# EEprog.net
KiCad netlist of a schematic drawn in EAGLE
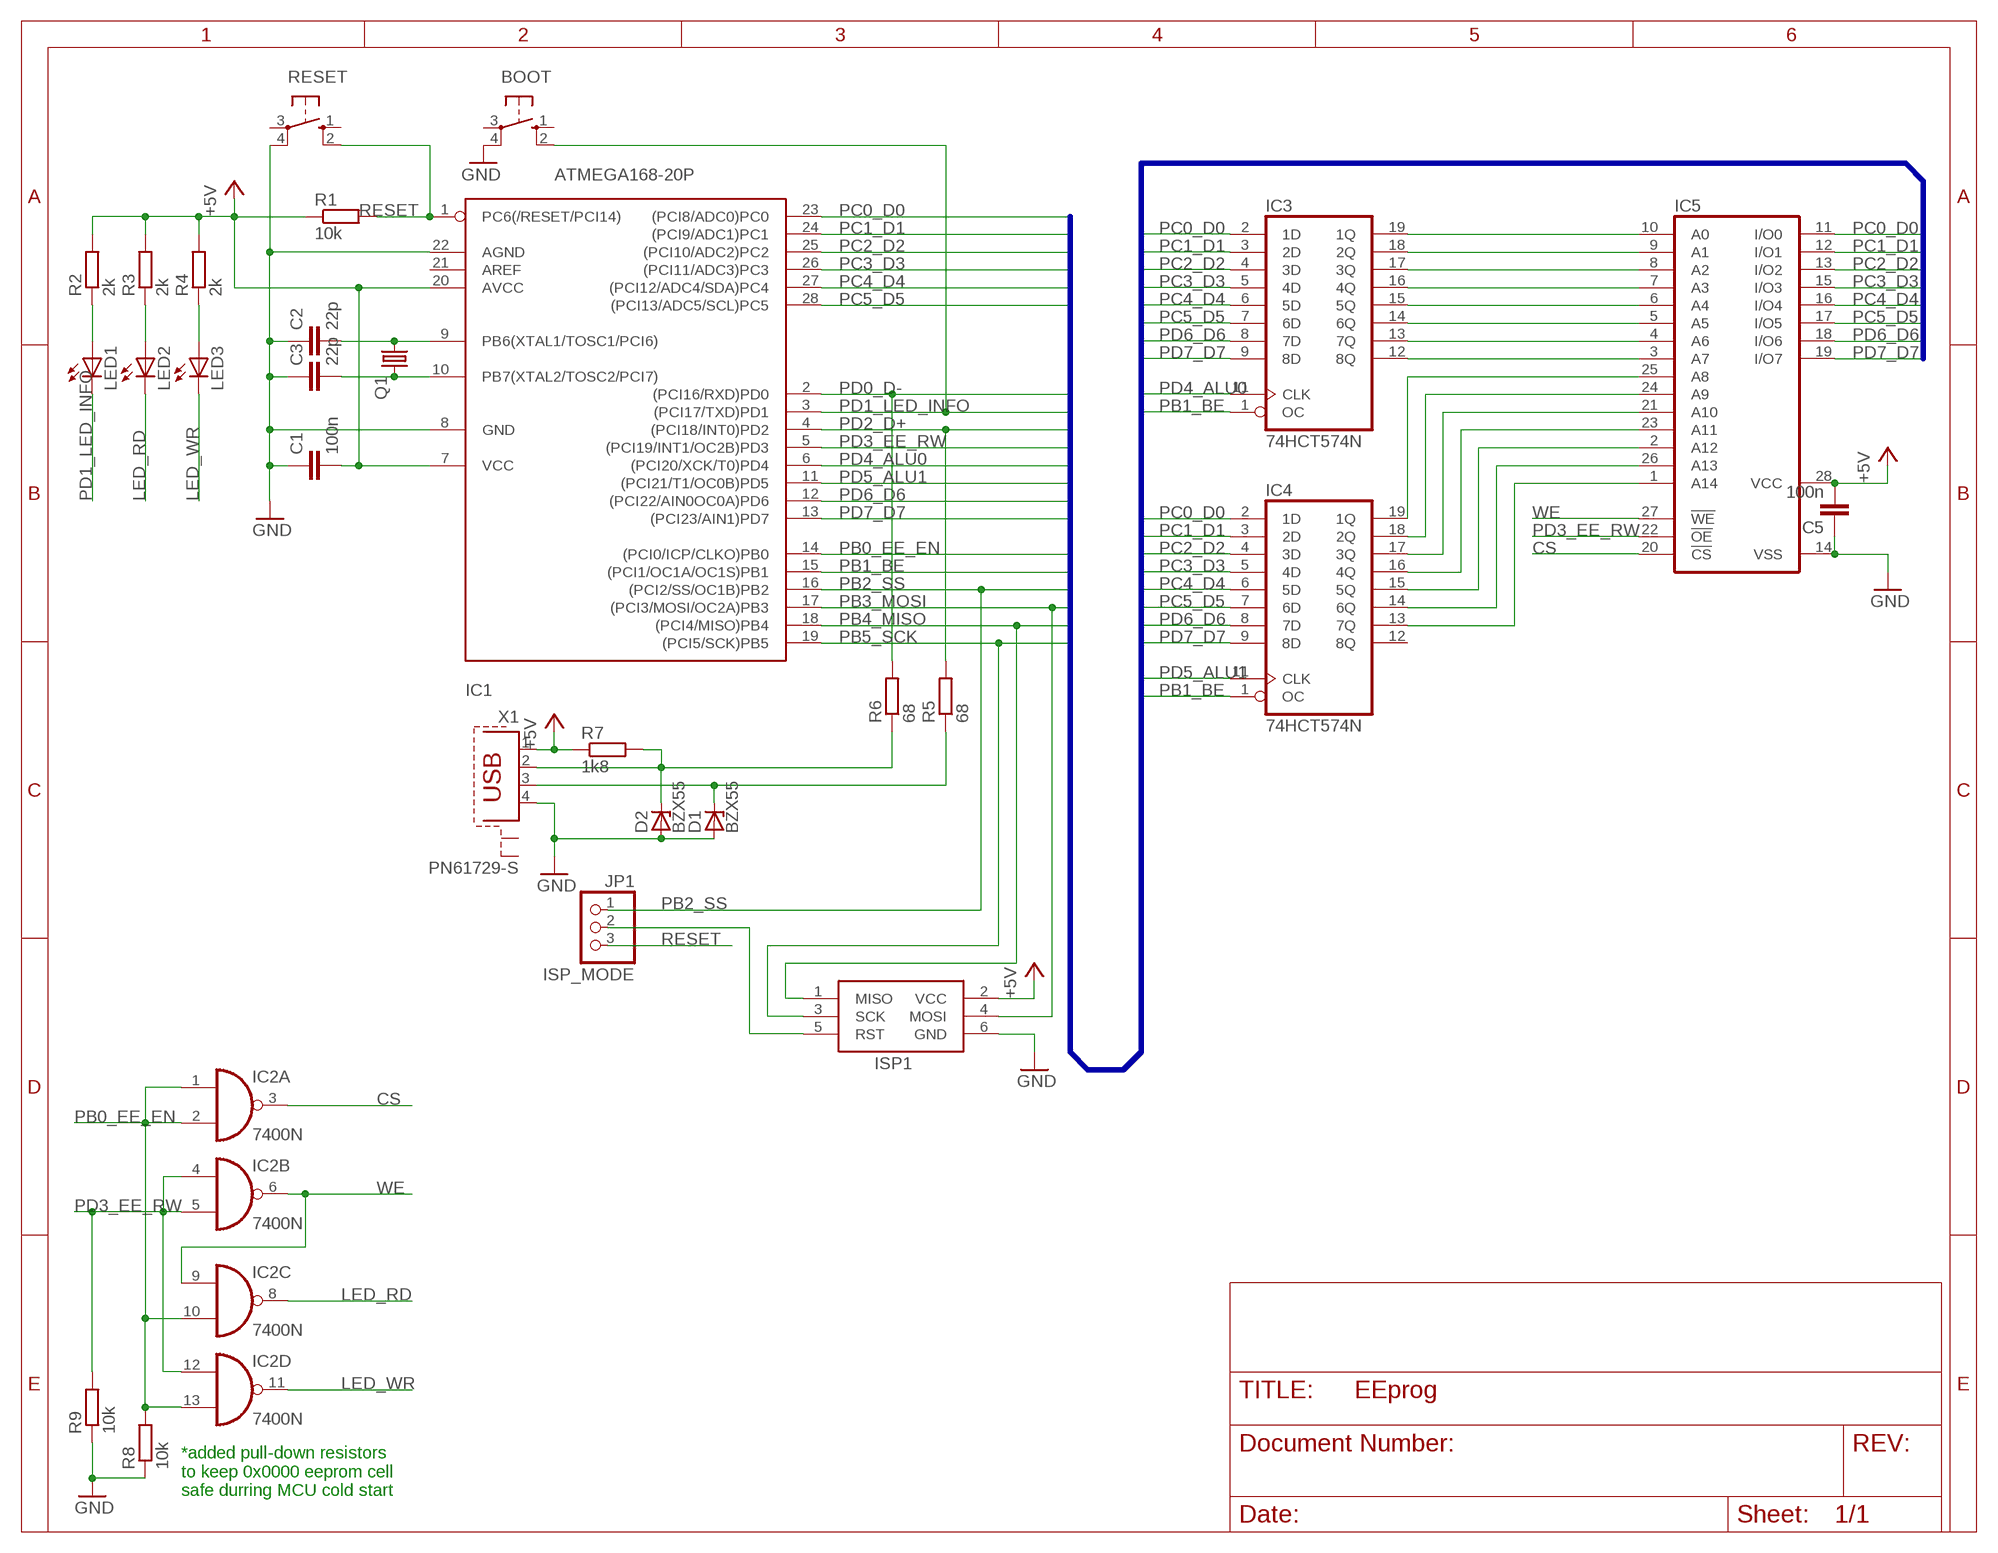
[diagram p0: schematic, sheet 1]

(export (version "E")
  (design (tool "Eeschema 10.0.6"))
  (components
    (comp (ref "BOOT")
      (value "10-XX")
      (footprint "eagle-import:B3F-10XX")
      (fields (field (name "MPN") "B3F-1000"))
      (libsource (lib "eagle-import") (part "10-XX"))
    )
    (comp (ref "C1")
      (value "100n")
      (footprint "eagle-import:C025-025X050")
      (libsource (lib "eagle-import") (part "C-EU025-025X050"))
    )
    (comp (ref "C2")
      (value "22p")
      (footprint "eagle-import:C025-025X050")
      (libsource (lib "eagle-import") (part "C-EU025-025X050"))
    )
    (comp (ref "C3")
      (value "22p")
      (footprint "eagle-import:C025-025X050")
      (libsource (lib "eagle-import") (part "C-EU025-025X050"))
    )
    (comp (ref "C5")
      (value "100n")
      (footprint "eagle-import:C025-025X050")
      (libsource (lib "eagle-import") (part "C-EU025-025X050"))
    )
    (comp (ref "D1")
      (value "BZX55")
      (footprint "eagle-import:DO35Z10")
      (libsource (lib "eagle-import") (part "BZX55"))
    )
    (comp (ref "D2")
      (value "BZX55")
      (footprint "eagle-import:DO35Z10")
      (libsource (lib "eagle-import") (part "BZX55"))
    )
    (comp (ref "IC1")
      (value "ATMEGA168-20P")
      (footprint "eagle-import:DIL28-3")
      (libsource (lib "eagle-import") (part "ATMEGA168P-20"))
    )
    (comp (ref "IC2")
      (value "7400N")
      (footprint "eagle-import:DIL14")
      (libsource (lib "eagle-import") (part "7400N"))
    )
    (comp (ref "IC3")
      (value "74HCT574N")
      (footprint "eagle-import:DIL20")
      (libsource (lib "eagle-import") (part "74574NHCT"))
    )
    (comp (ref "IC4")
      (value "74HCT574N")
      (footprint "eagle-import:DIL20")
      (libsource (lib "eagle-import") (part "74574NHCT"))
    )
    (comp (ref "IC5")
      (value "62256P")
      (footprint "eagle-import:DIL28-6")
      (libsource (lib "eagle-import") (part "62256P"))
    )
    (comp (ref "ISP1")
      (value "AVRISP-BOX")
      (footprint "eagle-import:AVRISP-BOX")
      (libsource (lib "eagle-import") (part "AVRISP-BOX"))
    )
    (comp (ref "JP1")
      (value "ISP_MODE")
      (footprint "eagle-import:1X03")
      (libsource (lib "eagle-import") (part "PINHD-1X3"))
    )
    (comp (ref "LED1")
      (value "LED3MM")
      (footprint "eagle-import:LED3MM")
      (libsource (lib "eagle-import") (part "LED3MM"))
    )
    (comp (ref "LED2")
      (value "LED3MM")
      (footprint "eagle-import:LED3MM")
      (libsource (lib "eagle-import") (part "LED3MM"))
    )
    (comp (ref "LED3")
      (value "LED3MM")
      (footprint "eagle-import:LED3MM")
      (libsource (lib "eagle-import") (part "LED3MM"))
    )
    (comp (ref "Q1")
      (value "CRYSTALHC49S")
      (footprint "eagle-import:HC49_S")
      (libsource (lib "eagle-import") (part "CRYSTALHC49S"))
    )
    (comp (ref "R1")
      (value "10k")
      (footprint "eagle-import:0204_7")
      (libsource (lib "eagle-import") (part "R-EU_0204/7"))
    )
    (comp (ref "R2")
      (value "2k")
      (footprint "eagle-import:0204_7")
      (libsource (lib "eagle-import") (part "R-EU_0204/7"))
    )
    (comp (ref "R3")
      (value "2k")
      (footprint "eagle-import:0204_7")
      (libsource (lib "eagle-import") (part "R-EU_0204/7"))
    )
    (comp (ref "R4")
      (value "2k")
      (footprint "eagle-import:0204_7")
      (libsource (lib "eagle-import") (part "R-EU_0204/7"))
    )
    (comp (ref "R5")
      (value "68")
      (footprint "eagle-import:0204_7")
      (libsource (lib "eagle-import") (part "R-EU_0204/7"))
    )
    (comp (ref "R6")
      (value "68")
      (footprint "eagle-import:0204_7")
      (libsource (lib "eagle-import") (part "R-EU_0204/7"))
    )
    (comp (ref "R7")
      (value "1k8")
      (footprint "eagle-import:0204_7")
      (libsource (lib "eagle-import") (part "R-EU_0204/7"))
    )
    (comp (ref "R8")
      (value "10k")
      (footprint "eagle-import:0204_7")
      (libsource (lib "eagle-import") (part "R-EU_0204/7"))
    )
    (comp (ref "R9")
      (value "10k")
      (footprint "eagle-import:0204_7")
      (libsource (lib "eagle-import") (part "R-EU_0204/7"))
    )
    (comp (ref "RESET")
      (value "10-XX")
      (footprint "eagle-import:B3F-10XX")
      (fields (field (name "MPN") "B3F-1000"))
      (libsource (lib "eagle-import") (part "10-XX"))
    )
    (comp (ref "X1")
      (value "PN61729-S")
      (footprint "eagle-import:PN61729-S")
      (libsource (lib "eagle-import") (part "PN61729-S"))
    )
  )
  (nets
    (net (code "1") (name "+5V") (class "Default")
      (node (ref "C1") (pin "2") (pinfunction "2_2") (pintype "passive"))
      (node (ref "C5") (pin "2") (pinfunction "2_2") (pintype "passive"))
      (node (ref "IC1") (pin "20") (pinfunction "AVCC_20") (pintype "bidirectional"))
      (node (ref "IC1") (pin "7") (pinfunction "VCC_7") (pintype "bidirectional"))
      (node (ref "IC5") (pin "28") (pinfunction "VCC_28") (pintype "power_in"))
      (node (ref "ISP1") (pin "2") (pinfunction "VCC_2") (pintype "power_in"))
      (node (ref "R1") (pin "1") (pinfunction "1_1") (pintype "passive"))
      (node (ref "R2") (pin "2") (pinfunction "2_2") (pintype "passive"))
      (node (ref "R3") (pin "2") (pinfunction "2_2") (pintype "passive"))
      (node (ref "R4") (pin "2") (pinfunction "2_2") (pintype "passive"))
      (node (ref "R7") (pin "1") (pinfunction "1_1") (pintype "passive"))
      (node (ref "X1") (pin "1") (pinfunction "1_1") (pintype "passive"))
    )
    (net (code "2") (name "/CS") (class "Default")
      (node (ref "IC2") (pin "3") (pinfunction "O_3") (pintype "output"))
      (node (ref "IC5") (pin "20") (pinfunction "~{CS}_20") (pintype "input"))
    )
    (net (code "3") (name "/LED_RD") (class "Default")
      (node (ref "IC2") (pin "8") (pinfunction "O_8") (pintype "output"))
      (node (ref "LED2") (pin "K") (pinfunction "C_K") (pintype "passive"))
    )
    (net (code "4") (name "/LED_WR") (class "Default")
      (node (ref "IC2") (pin "11") (pinfunction "O_11") (pintype "output"))
      (node (ref "LED3") (pin "K") (pinfunction "C_K") (pintype "passive"))
    )
    (net (code "5") (name "/PB0_EE_EN") (class "Default")
      (node (ref "IC1") (pin "14") (pinfunction "(PCI0/ICP/CLKO)PB0_14") (pintype "bidirectional"))
      (node (ref "IC2") (pin "1") (pinfunction "I0_1") (pintype "input"))
      (node (ref "IC2") (pin "10") (pinfunction "I1_10") (pintype "input"))
      (node (ref "IC2") (pin "13") (pinfunction "I1_13") (pintype "input"))
      (node (ref "IC2") (pin "2") (pinfunction "I1_2") (pintype "input"))
      (node (ref "R8") (pin "2") (pinfunction "2_2") (pintype "passive"))
    )
    (net (code "6") (name "/PB1_BE") (class "Default")
      (node (ref "IC1") (pin "15") (pinfunction "(PCI1/OC1A/OC1S)PB1_15") (pintype "bidirectional"))
      (node (ref "IC3") (pin "1") (pinfunction "OC_1") (pintype "input"))
      (node (ref "IC4") (pin "1") (pinfunction "OC_1") (pintype "input"))
    )
    (net (code "7") (name "/PB2_SS") (class "Default")
      (node (ref "IC1") (pin "16") (pinfunction "(PCI2/SS/OC1B)PB2_16") (pintype "bidirectional"))
      (node (ref "JP1") (pin "1") (pinfunction "1_1") (pintype "passive"))
    )
    (net (code "8") (name "/PB3_MOSI") (class "Default")
      (node (ref "IC1") (pin "17") (pinfunction "(PCI3/MOSI/OC2A)PB3_17") (pintype "bidirectional"))
      (node (ref "ISP1") (pin "4") (pinfunction "MOSI_4") (pintype "output"))
    )
    (net (code "9") (name "/PB4_MISO") (class "Default")
      (node (ref "IC1") (pin "18") (pinfunction "(PCI4/MISO)PB4_18") (pintype "bidirectional"))
      (node (ref "ISP1") (pin "1") (pinfunction "MISO_1") (pintype "input"))
    )
    (net (code "10") (name "/PB5_SCK") (class "Default")
      (node (ref "IC1") (pin "19") (pinfunction "(PCI5/SCK)PB5_19") (pintype "bidirectional"))
      (node (ref "ISP1") (pin "3") (pinfunction "SCK_3") (pintype "output"))
    )
    (net (code "11") (name "/PC0_D0") (class "Default")
      (node (ref "IC1") (pin "23") (pinfunction "(PCI8/ADC0)PC0_23") (pintype "bidirectional"))
      (node (ref "IC3") (pin "2") (pinfunction "1D_2") (pintype "input"))
      (node (ref "IC4") (pin "2") (pinfunction "1D_2") (pintype "input"))
      (node (ref "IC5") (pin "11") (pinfunction "I/O0_11") (pintype "bidirectional"))
    )
    (net (code "12") (name "/PC1_D1") (class "Default")
      (node (ref "IC1") (pin "24") (pinfunction "(PCI9/ADC1)PC1_24") (pintype "bidirectional"))
      (node (ref "IC3") (pin "3") (pinfunction "2D_3") (pintype "input"))
      (node (ref "IC4") (pin "3") (pinfunction "2D_3") (pintype "input"))
      (node (ref "IC5") (pin "12") (pinfunction "I/O1_12") (pintype "bidirectional"))
    )
    (net (code "13") (name "/PC2_D2") (class "Default")
      (node (ref "IC1") (pin "25") (pinfunction "(PCI10/ADC2)PC2_25") (pintype "bidirectional"))
      (node (ref "IC3") (pin "4") (pinfunction "3D_4") (pintype "input"))
      (node (ref "IC4") (pin "4") (pinfunction "3D_4") (pintype "input"))
      (node (ref "IC5") (pin "13") (pinfunction "I/O2_13") (pintype "bidirectional"))
    )
    (net (code "14") (name "/PC3_D3") (class "Default")
      (node (ref "IC1") (pin "26") (pinfunction "(PCI11/ADC3)PC3_26") (pintype "bidirectional"))
      (node (ref "IC3") (pin "5") (pinfunction "4D_5") (pintype "input"))
      (node (ref "IC4") (pin "5") (pinfunction "4D_5") (pintype "input"))
      (node (ref "IC5") (pin "15") (pinfunction "I/O3_15") (pintype "bidirectional"))
    )
    (net (code "15") (name "/PC4_D4") (class "Default")
      (node (ref "IC1") (pin "27") (pinfunction "(PCI12/ADC4/SDA)PC4_27") (pintype "bidirectional"))
      (node (ref "IC3") (pin "6") (pinfunction "5D_6") (pintype "input"))
      (node (ref "IC4") (pin "6") (pinfunction "5D_6") (pintype "input"))
      (node (ref "IC5") (pin "16") (pinfunction "I/O4_16") (pintype "bidirectional"))
    )
    (net (code "16") (name "/PC5_D5") (class "Default")
      (node (ref "IC1") (pin "28") (pinfunction "(PCI13/ADC5/SCL)PC5_28") (pintype "bidirectional"))
      (node (ref "IC3") (pin "7") (pinfunction "6D_7") (pintype "input"))
      (node (ref "IC4") (pin "7") (pinfunction "6D_7") (pintype "input"))
      (node (ref "IC5") (pin "17") (pinfunction "I/O5_17") (pintype "bidirectional"))
    )
    (net (code "17") (name "/PD0_D-") (class "Default")
      (node (ref "IC1") (pin "2") (pinfunction "(PCI16/RXD)PD0_2") (pintype "bidirectional"))
      (node (ref "R6") (pin "2") (pinfunction "2_2") (pintype "passive"))
    )
    (net (code "18") (name "/PD1_LED_INFO") (class "Default")
      (node (ref "BOOT") (pin "2") (pinfunction "S1_2") (pintype "passive"))
      (node (ref "IC1") (pin "3") (pinfunction "(PCI17/TXD)PD1_3") (pintype "bidirectional"))
      (node (ref "LED1") (pin "K") (pinfunction "C_K") (pintype "passive"))
    )
    (net (code "19") (name "/PD2_D+") (class "Default")
      (node (ref "IC1") (pin "4") (pinfunction "(PCI18/INT0)PD2_4") (pintype "bidirectional"))
      (node (ref "R5") (pin "2") (pinfunction "2_2") (pintype "passive"))
    )
    (net (code "20") (name "/PD3_EE_RW") (class "Default")
      (node (ref "IC1") (pin "5") (pinfunction "(PCI19/INT1/OC2B)PD3_5") (pintype "bidirectional"))
      (node (ref "IC2") (pin "12") (pinfunction "I0_12") (pintype "input"))
      (node (ref "IC2") (pin "4") (pinfunction "I0_4") (pintype "input"))
      (node (ref "IC2") (pin "5") (pinfunction "I1_5") (pintype "input"))
      (node (ref "IC5") (pin "22") (pinfunction "~{OE}_22") (pintype "input"))
      (node (ref "R9") (pin "2") (pinfunction "2_2") (pintype "passive"))
    )
    (net (code "21") (name "/PD4_ALU0") (class "Default")
      (node (ref "IC1") (pin "6") (pinfunction "(PCI20/XCK/T0)PD4_6") (pintype "bidirectional"))
      (node (ref "IC3") (pin "11") (pinfunction "CLK_11") (pintype "input"))
    )
    (net (code "22") (name "/PD5_ALU1") (class "Default")
      (node (ref "IC1") (pin "11") (pinfunction "(PCI21/T1/OC0B)PD5_11") (pintype "bidirectional"))
      (node (ref "IC4") (pin "11") (pinfunction "CLK_11") (pintype "input"))
    )
    (net (code "23") (name "/PD6_D6") (class "Default")
      (node (ref "IC1") (pin "12") (pinfunction "(PCI22/AIN0OC0A)PD6_12") (pintype "bidirectional"))
      (node (ref "IC3") (pin "8") (pinfunction "7D_8") (pintype "input"))
      (node (ref "IC4") (pin "8") (pinfunction "7D_8") (pintype "input"))
      (node (ref "IC5") (pin "18") (pinfunction "I/O6_18") (pintype "bidirectional"))
    )
    (net (code "24") (name "/PD7_D7") (class "Default")
      (node (ref "IC1") (pin "13") (pinfunction "(PCI23/AIN1)PD7_13") (pintype "bidirectional"))
      (node (ref "IC3") (pin "9") (pinfunction "8D_9") (pintype "input"))
      (node (ref "IC4") (pin "9") (pinfunction "8D_9") (pintype "input"))
      (node (ref "IC5") (pin "19") (pinfunction "I/O7_19") (pintype "bidirectional"))
    )
    (net (code "25") (name "/RESET") (class "Default")
      (node (ref "IC1") (pin "1") (pinfunction "PC6(/RESET/PCI14)_1") (pintype "bidirectional"))
      (node (ref "JP1") (pin "3") (pinfunction "3_3") (pintype "passive"))
      (node (ref "R1") (pin "2") (pinfunction "2_2") (pintype "passive"))
      (node (ref "RESET") (pin "2") (pinfunction "S1_2") (pintype "passive"))
    )
    (net (code "26") (name "/WE") (class "Default")
      (node (ref "IC2") (pin "6") (pinfunction "O_6") (pintype "output"))
      (node (ref "IC2") (pin "9") (pinfunction "I0_9") (pintype "input"))
      (node (ref "IC5") (pin "27") (pinfunction "~{WE}_27") (pintype "input"))
    )
    (net (code "27") (name "GND") (class "Default")
      (node (ref "BOOT") (pin "4") (pinfunction "P1_4") (pintype "passive"))
      (node (ref "C1") (pin "1") (pinfunction "1_1") (pintype "passive"))
      (node (ref "C2") (pin "1") (pinfunction "1_1") (pintype "passive"))
      (node (ref "C3") (pin "1") (pinfunction "1_1") (pintype "passive"))
      (node (ref "C5") (pin "1") (pinfunction "1_1") (pintype "passive"))
      (node (ref "D1") (pin "A") (pinfunction "A_A") (pintype "passive"))
      (node (ref "D2") (pin "A") (pinfunction "A_A") (pintype "passive"))
      (node (ref "IC1") (pin "22") (pinfunction "AGND_22") (pintype "bidirectional"))
      (node (ref "IC1") (pin "8") (pinfunction "GND_8") (pintype "bidirectional"))
      (node (ref "IC5") (pin "14") (pinfunction "VSS_14") (pintype "power_in"))
      (node (ref "ISP1") (pin "6") (pinfunction "GND_6") (pintype "power_in"))
      (node (ref "R8") (pin "1") (pinfunction "1_1") (pintype "passive"))
      (node (ref "R9") (pin "1") (pinfunction "1_1") (pintype "passive"))
      (node (ref "RESET") (pin "4") (pinfunction "P1_4") (pintype "passive"))
      (node (ref "X1") (pin "4") (pinfunction "4_4") (pintype "passive"))
    )
    (net (code "28") (name "Net-(D1-PadC)") (class "Default")
      (node (ref "D1") (pin "C") (pinfunction "C_C") (pintype "passive"))
      (node (ref "R5") (pin "1") (pinfunction "1_1") (pintype "passive"))
      (node (ref "X1") (pin "3") (pinfunction "3_3") (pintype "passive"))
    )
    (net (code "29") (name "Net-(D2-PadC)") (class "Default")
      (node (ref "D2") (pin "C") (pinfunction "C_C") (pintype "passive"))
      (node (ref "R6") (pin "1") (pinfunction "1_1") (pintype "passive"))
      (node (ref "R7") (pin "2") (pinfunction "2_2") (pintype "passive"))
      (node (ref "X1") (pin "2") (pinfunction "2_2") (pintype "passive"))
    )
    (net (code "30") (name "Net-(IC1-PB6(XTAL1{slash}TOSC1{slash}PCI6))") (class "Default")
      (node (ref "C2") (pin "2") (pinfunction "2_2") (pintype "passive"))
      (node (ref "IC1") (pin "9") (pinfunction "PB6(XTAL1/TOSC1/PCI6)_9") (pintype "bidirectional"))
      (node (ref "Q1") (pin "1") (pinfunction "1_1") (pintype "passive"))
    )
    (net (code "31") (name "Net-(IC1-PB7(XTAL2{slash}TOSC2{slash}PCI7))") (class "Default")
      (node (ref "C3") (pin "2") (pinfunction "2_2") (pintype "passive"))
      (node (ref "IC1") (pin "10") (pinfunction "PB7(XTAL2/TOSC2/PCI7)_10") (pintype "bidirectional"))
      (node (ref "Q1") (pin "2") (pinfunction "2_2") (pintype "passive"))
    )
    (net (code "32") (name "Net-(IC3A-1Q)") (class "Default")
      (node (ref "IC3") (pin "19") (pinfunction "1Q_19") (pintype "tri_state"))
      (node (ref "IC5") (pin "10") (pinfunction "A0_10") (pintype "input"))
    )
    (net (code "33") (name "Net-(IC3A-2Q)") (class "Default")
      (node (ref "IC3") (pin "18") (pinfunction "2Q_18") (pintype "tri_state"))
      (node (ref "IC5") (pin "9") (pinfunction "A1_9") (pintype "input"))
    )
    (net (code "34") (name "Net-(IC3A-3Q)") (class "Default")
      (node (ref "IC3") (pin "17") (pinfunction "3Q_17") (pintype "tri_state"))
      (node (ref "IC5") (pin "8") (pinfunction "A2_8") (pintype "input"))
    )
    (net (code "35") (name "Net-(IC3A-4Q)") (class "Default")
      (node (ref "IC3") (pin "16") (pinfunction "4Q_16") (pintype "tri_state"))
      (node (ref "IC5") (pin "7") (pinfunction "A3_7") (pintype "input"))
    )
    (net (code "36") (name "Net-(IC3A-5Q)") (class "Default")
      (node (ref "IC3") (pin "15") (pinfunction "5Q_15") (pintype "tri_state"))
      (node (ref "IC5") (pin "6") (pinfunction "A4_6") (pintype "input"))
    )
    (net (code "37") (name "Net-(IC3A-6Q)") (class "Default")
      (node (ref "IC3") (pin "14") (pinfunction "6Q_14") (pintype "tri_state"))
      (node (ref "IC5") (pin "5") (pinfunction "A5_5") (pintype "input"))
    )
    (net (code "38") (name "Net-(IC3A-7Q)") (class "Default")
      (node (ref "IC3") (pin "13") (pinfunction "7Q_13") (pintype "tri_state"))
      (node (ref "IC5") (pin "4") (pinfunction "A6_4") (pintype "input"))
    )
    (net (code "39") (name "Net-(IC3A-8Q)") (class "Default")
      (node (ref "IC3") (pin "12") (pinfunction "8Q_12") (pintype "tri_state"))
      (node (ref "IC5") (pin "3") (pinfunction "A7_3") (pintype "input"))
    )
    (net (code "40") (name "Net-(IC4A-1Q)") (class "Default")
      (node (ref "IC4") (pin "19") (pinfunction "1Q_19") (pintype "tri_state"))
      (node (ref "IC5") (pin "25") (pinfunction "A8_25") (pintype "input"))
    )
    (net (code "41") (name "Net-(IC4A-2Q)") (class "Default")
      (node (ref "IC4") (pin "18") (pinfunction "2Q_18") (pintype "tri_state"))
      (node (ref "IC5") (pin "24") (pinfunction "A9_24") (pintype "input"))
    )
    (net (code "42") (name "Net-(IC4A-3Q)") (class "Default")
      (node (ref "IC4") (pin "17") (pinfunction "3Q_17") (pintype "tri_state"))
      (node (ref "IC5") (pin "21") (pinfunction "A10_21") (pintype "input"))
    )
    (net (code "43") (name "Net-(IC4A-4Q)") (class "Default")
      (node (ref "IC4") (pin "16") (pinfunction "4Q_16") (pintype "tri_state"))
      (node (ref "IC5") (pin "23") (pinfunction "A11_23") (pintype "input"))
    )
    (net (code "44") (name "Net-(IC4A-5Q)") (class "Default")
      (node (ref "IC4") (pin "15") (pinfunction "5Q_15") (pintype "tri_state"))
      (node (ref "IC5") (pin "2") (pinfunction "A12_2") (pintype "input"))
    )
    (net (code "45") (name "Net-(IC4A-6Q)") (class "Default")
      (node (ref "IC4") (pin "14") (pinfunction "6Q_14") (pintype "tri_state"))
      (node (ref "IC5") (pin "26") (pinfunction "A13_26") (pintype "input"))
    )
    (net (code "46") (name "Net-(IC4A-7Q)") (class "Default")
      (node (ref "IC4") (pin "13") (pinfunction "7Q_13") (pintype "tri_state"))
      (node (ref "IC5") (pin "1") (pinfunction "A14_1") (pintype "input"))
    )
    (net (code "47") (name "Net-(ISP1-RST)") (class "Default")
      (node (ref "ISP1") (pin "5") (pinfunction "RST_5") (pintype "output"))
      (node (ref "JP1") (pin "2") (pinfunction "2_2") (pintype "passive"))
    )
    (net (code "48") (name "Net-(LED1-PadA)") (class "Default")
      (node (ref "LED1") (pin "A") (pinfunction "A_A") (pintype "passive"))
      (node (ref "R2") (pin "1") (pinfunction "1_1") (pintype "passive"))
    )
    (net (code "49") (name "Net-(LED2-PadA)") (class "Default")
      (node (ref "LED2") (pin "A") (pinfunction "A_A") (pintype "passive"))
      (node (ref "R3") (pin "1") (pinfunction "1_1") (pintype "passive"))
    )
    (net (code "50") (name "Net-(LED3-PadA)") (class "Default")
      (node (ref "LED3") (pin "A") (pinfunction "A_A") (pintype "passive"))
      (node (ref "R4") (pin "1") (pinfunction "1_1") (pintype "passive"))
    )
    (net (code "51") (name "unconnected-(BOOT-P-Pad3)") (class "Default")
      (node (ref "BOOT") (pin "3") (pinfunction "P_3") (pintype "passive"))
    )
    (net (code "52") (name "unconnected-(BOOT-S-Pad1)") (class "Default")
      (node (ref "BOOT") (pin "1") (pinfunction "S_1") (pintype "passive"))
    )
    (net (code "53") (name "unconnected-(IC1-AREF-Pad21)") (class "Default")
      (node (ref "IC1") (pin "21") (pinfunction "AREF_21") (pintype "bidirectional"))
    )
    (net (code "54") (name "unconnected-(IC4A-8Q-Pad12)") (class "Default")
      (node (ref "IC4") (pin "12") (pinfunction "8Q_12") (pintype "tri_state"))
    )
    (net (code "55") (name "unconnected-(RESET-P-Pad3)") (class "Default")
      (node (ref "RESET") (pin "3") (pinfunction "P_3") (pintype "passive"))
    )
    (net (code "56") (name "unconnected-(RESET-S-Pad1)") (class "Default")
      (node (ref "RESET") (pin "1") (pinfunction "S_1") (pintype "passive"))
    )
    (net (code "57") (name "unconnected-(X1-PadS1)") (class "Default")
      (node (ref "X1") (pin "S1") (pinfunction "S1_S1") (pintype "passive"))
    )
    (net (code "58") (name "unconnected-(X1-PadS2)") (class "Default")
      (node (ref "X1") (pin "S2") (pinfunction "S2_S2") (pintype "passive"))
    )
  )
)
